# PMP20873E1_Bias.net
KiCad netlist of a schematic drawn in Altium Designer
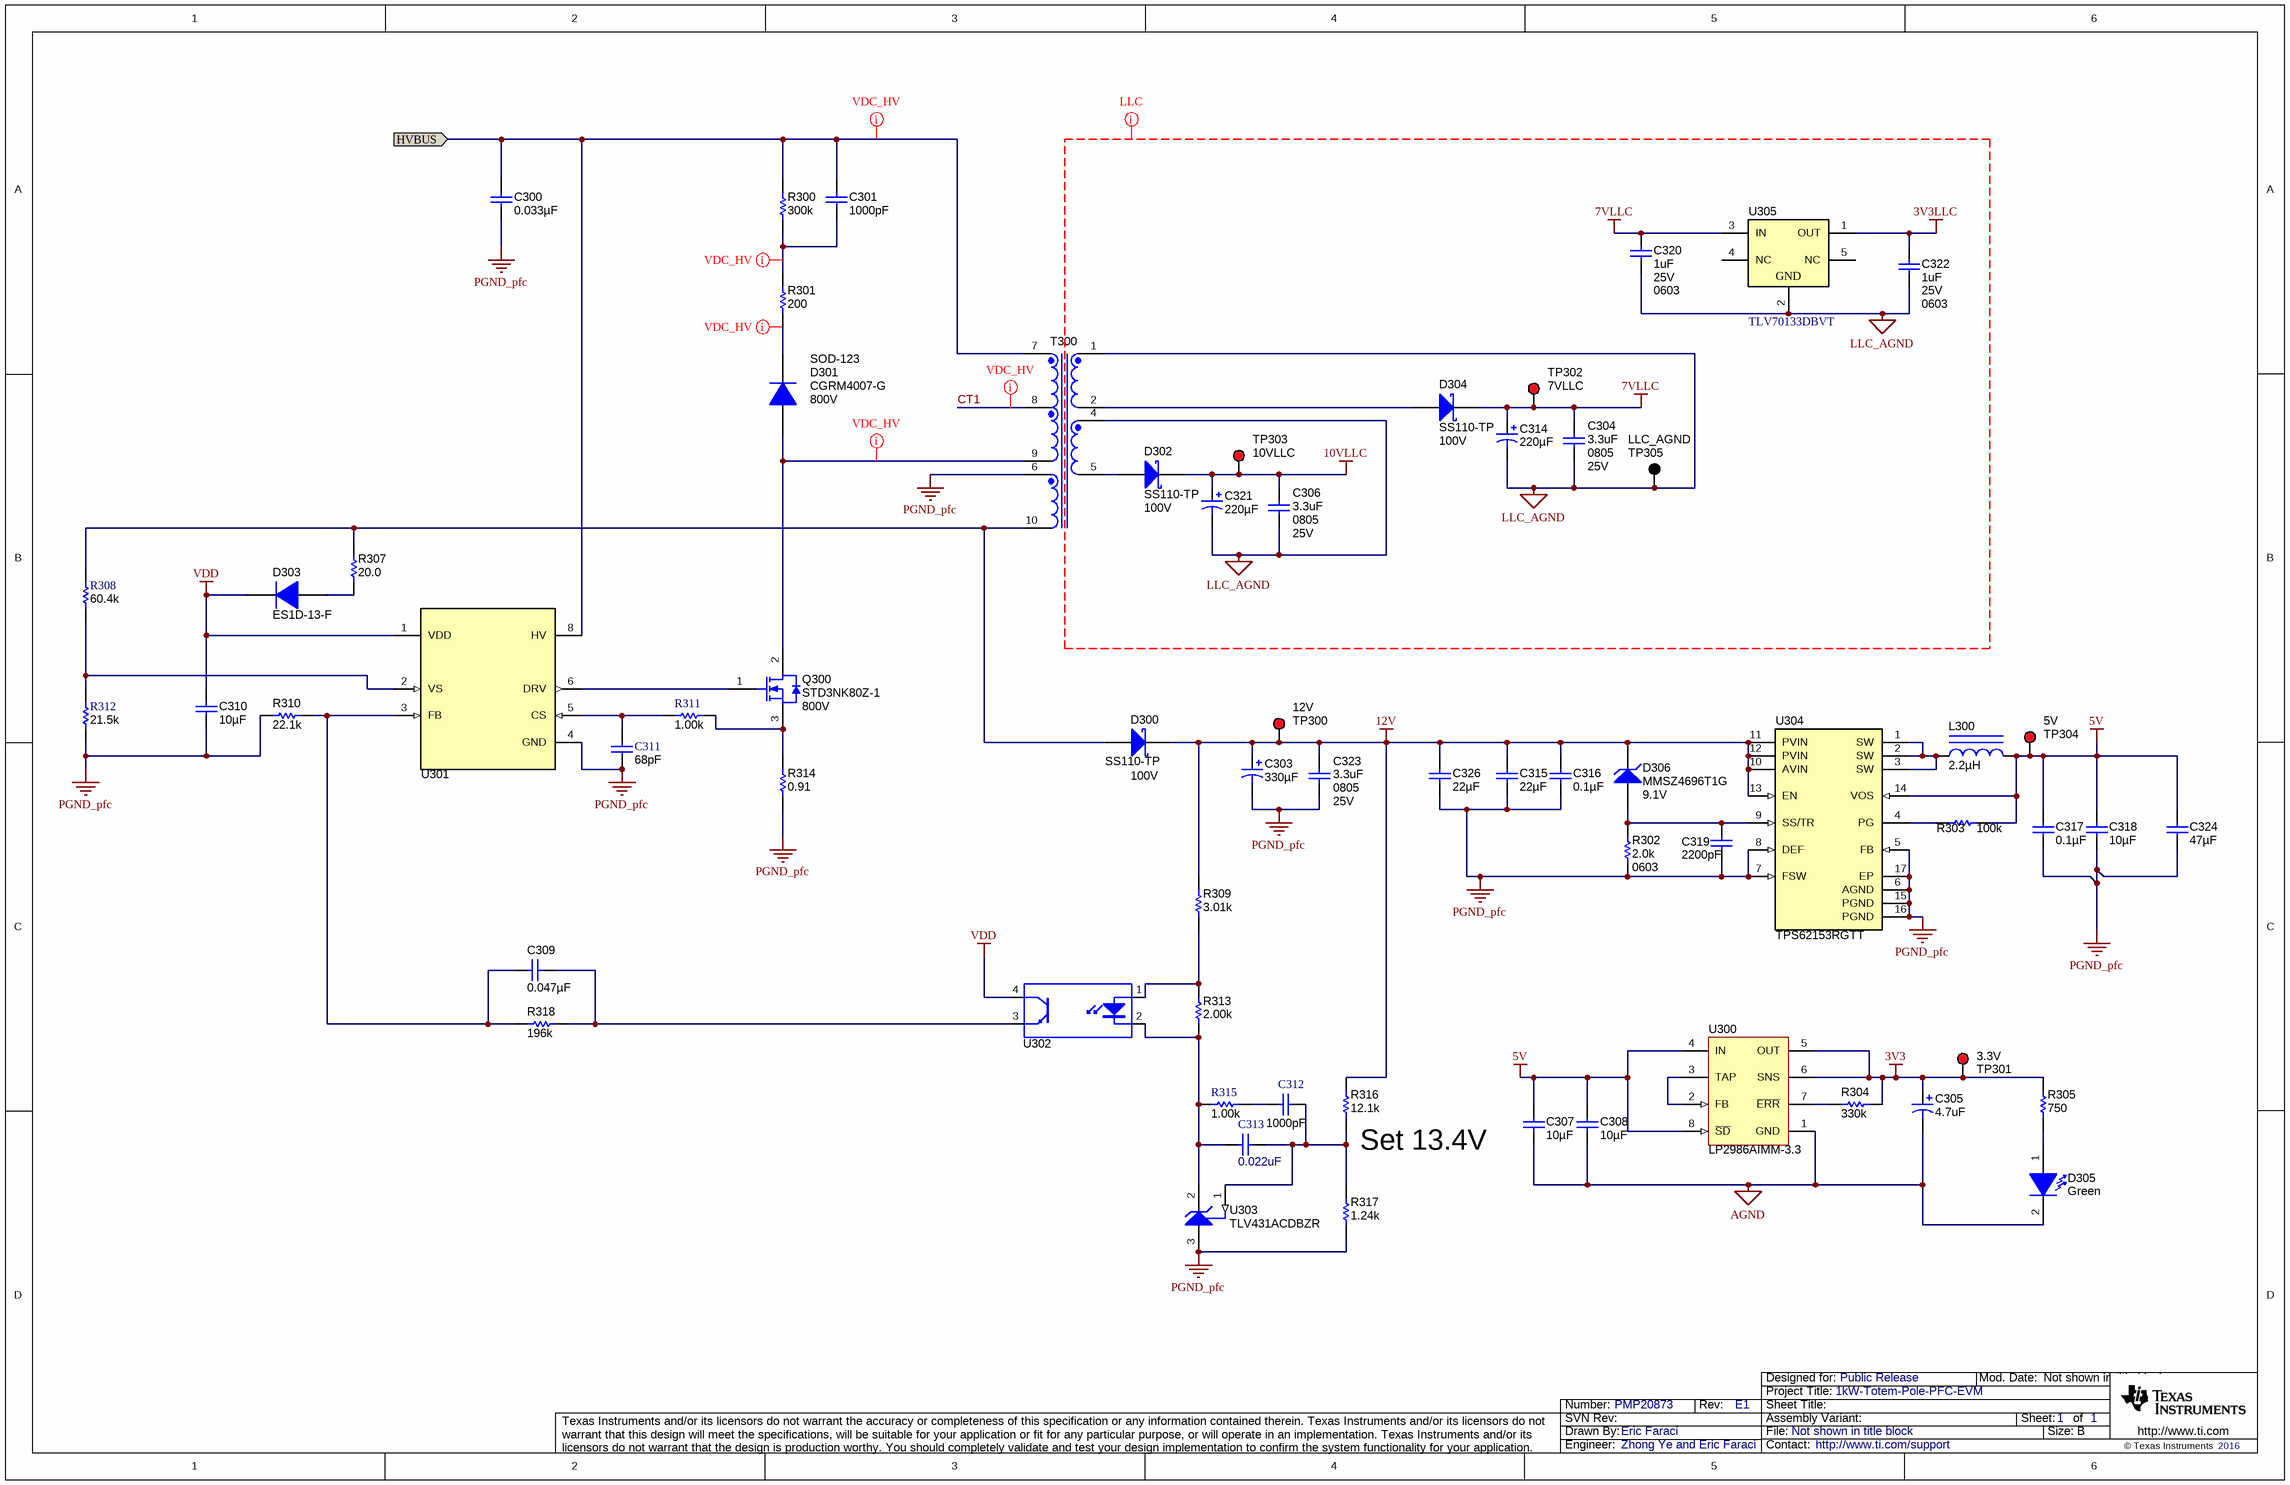
[diagram p0: PMP20873E1_Bias.SchDoc]

(export (version "E")
  (design (tool "Eeschema 10.0.6"))
  (components
    (comp (ref "C300")
      (value "GRM32DR72J333KW01L")
      (footprint "1210")
      (description "CAP, CERM, 0.033 µF, 630 V, +/- 10%, X7R, 1210")
      (fields
        (field (name "VALUEDISPLAYED") "0.033µF")
        (field (name "MANUFACTURER") "MuRata")
        (field (name "PUBLISHER") "Texas Instruments")
      )
      (libsource (lib "Capacitor_Ceramic") (part "GRM32DR72J333KW01L"))
    )
    (comp (ref "C301")
      (value "C2012X7R2E102K")
      (footprint "0805_HV")
      (description "CAP, CERM, 1000 pF, 250 V, +/- 10%, X7R, 0805")
      (fields
        (field (name "VALUEDISPLAYED") "1000pF")
        (field (name "MANUFACTURER") "TDK")
        (field (name "PUBLISHER") "Texas Instruments")
      )
      (libsource (lib "Capacitor_Ceramic") (part "C2012X7R2E102K"))
    )
    (comp (ref "C303")
      (value "25ZL330MEFC10X12.5")
      (footprint "ZL_1000x1250")
      (description "CAP, AL, 330 µF, 25 V, +/- 20%, 0.053 ohm, TH")
      (fields
        (field (name "VALUEDISPLAYED") "330µF")
        (field (name "MANUFACTURER") "Rubycon")
        (field (name "PUBLISHER") "Texas Instruments")
      )
      (libsource (lib "Capacitor_Aluminum") (part "25ZL330MEFC10X12.5"))
    )
    (comp (ref "C304")
      (value "GRM21BR71E335KA73L")
      (footprint "0805_HV")
      (description "CAP, CERM, 3.3uF, 25V, +/-10%, X7R, 0805")
      (fields
        (field (name "VALUEDISPLAYED") "3.3uF")
        (field (name "MANUFACTURER") "MuRata")
        (field (name "PACKAGEREFERENCE") "0805")
        (field (name "VALUE2") "25V")
        (field (name "PUBLISHER") "Texas Instruments")
      )
      (libsource (lib "Capacitor_Ceramic") (part "GRM21BR71E335KA73L"))
    )
    (comp (ref "C305")
      (value "293D475X9010B2TE3")
      (footprint "3528-21")
      (description "CAP, TA, 4.7uF, 10V, +/-10%, 3.4 ohm, SMD")
      (fields
        (field (name "VALUEDISPLAYED") "4.7uF")
        (field (name "MANUFACTURER") "Vishay-Sprague")
        (field (name "PUBLISHER") "Texas Instruments")
      )
      (libsource (lib "Capacitor_Tantalum") (part "293D475X9010B2TE3"))
    )
    (comp (ref "C306")
      (value "GRM21BR71E335KA73L")
      (footprint "0805_HV")
      (description "CAP, CERM, 3.3uF, 25V, +/-10%, X7R, 0805")
      (fields
        (field (name "VALUEDISPLAYED") "3.3uF")
        (field (name "MANUFACTURER") "MuRata")
        (field (name "PACKAGEREFERENCE") "0805")
        (field (name "VALUE2") "25V")
        (field (name "PUBLISHER") "Texas Instruments")
      )
      (libsource (lib "Capacitor_Ceramic") (part "GRM21BR71E335KA73L"))
    )
    (comp (ref "C307")
      (value "C0805C106K8PACTU")
      (footprint "0805_HV")
      (description "CAP, CERM, 10 µF, 10 V, +/- 10%, X5R, 0805")
      (fields
        (field (name "VALUEDISPLAYED") "10µF")
        (field (name "MANUFACTURER") "Kemet")
        (field (name "PUBLISHER") "Texas Instruments")
      )
      (libsource (lib "Capacitor_Ceramic") (part "C0805C106K8PACTU"))
    )
    (comp (ref "C308")
      (value "C0805C106K8PACTU")
      (footprint "0805_HV")
      (description "CAP, CERM, 10 µF, 10 V, +/- 10%, X5R, 0805")
      (fields
        (field (name "VALUEDISPLAYED") "10µF")
        (field (name "MANUFACTURER") "Kemet")
        (field (name "PUBLISHER") "Texas Instruments")
      )
      (libsource (lib "Capacitor_Ceramic") (part "C0805C106K8PACTU"))
    )
    (comp (ref "C309")
      (value "C0805C473K5RACTU")
      (footprint "0805_HV")
      (description "CAP, CERM, 0.047 µF, 50 V, +/- 10%, X7R, 0805")
      (fields
        (field (name "VALUEDISPLAYED") "0.047µF")
        (field (name "MANUFACTURER") "Kemet")
        (field (name "PUBLISHER") "Texas Instruments")
      )
      (libsource (lib "Capacitor_Ceramic") (part "C0805C473K5RACTU"))
    )
    (comp (ref "C310")
      (value "GRM31CR71E106KA12L")
      (footprint "1206")
      (description "CAP, CERM, 10 µF, 25 V, +/- 10%, X7R, 1206")
      (fields
        (field (name "VALUEDISPLAYED") "10µF")
        (field (name "MANUFACTURER") "MuRata")
        (field (name "PUBLISHER") "Texas Instruments")
      )
      (libsource (lib "Capacitor_Ceramic") (part "GRM31CR71E106KA12L"))
    )
    (comp (ref "C311")
      (value "06035A680JAT2A")
      (footprint "0603")
      (description "CAP, CERM, 68pF, 50V, +/-5%, C0G/NP0, 0603")
      (fields
        (field (name "VALUEDISPLAYED") "68pF")
        (field (name "MANUFACTURER") "AVX")
        (field (name "PUBLISHER") "Texas Instruments")
      )
      (libsource (lib "Capacitor_Ceramic") (part "06035A680JAT2A"))
    )
    (comp (ref "C312")
      (value "06035A102KAT2A")
      (footprint "0603")
      (description "CAP, CERM, 1000pF, 50V, +/-10%, C0G/NP0, 0603")
      (fields
        (field (name "VALUEDISPLAYED") "1000pF")
        (field (name "MANUFACTURER") "AVX")
        (field (name "PUBLISHER") "Texas Instruments")
      )
      (libsource (lib "Capacitor_Ceramic") (part "06035A102KAT2A"))
    )
    (comp (ref "C313")
      (value "C0603C223K3RACTU")
      (footprint "0603")
      (description "CAP, CERM, 0.022uF, 25V, +/-10%, X7R, 0603")
      (fields
        (field (name "VALUEDISPLAYED") "0.022uF")
        (field (name "MANUFACTURER") "Kemet")
        (field (name "PUBLISHER") "Texas Instruments")
      )
      (libsource (lib "Capacitor_Ceramic") (part "C0603C223K3RACTU"))
    )
    (comp (ref "C314")
      (value "TPSV227K016R0050")
      (footprint "7361-38")
      (description "CAP, TA, 220 µF, 16 V, +/- 10%, 0.05 ohm, SMD")
      (fields
        (field (name "VALUEDISPLAYED") "220µF")
        (field (name "MANUFACTURER") "AVX")
        (field (name "PUBLISHER") "Texas Instruments")
      )
      (libsource (lib "Capacitor_Tantalum") (part "TPSV227K016R0050"))
    )
    (comp (ref "C315")
      (value "1206YD226MAT2A")
      (footprint "1206")
      (description "CAP, CERM, 22 µF, 16 V, +/- 20%, X5R, 1206")
      (fields
        (field (name "VALUEDISPLAYED") "22µF")
        (field (name "MANUFACTURER") "AVX")
        (field (name "PUBLISHER") "Texas Instruments")
      )
      (libsource (lib "Capacitor_Ceramic") (part "1206YD226MAT2A"))
    )
    (comp (ref "C316")
      (value "C1005X7R1H104K")
      (footprint "0402")
      (description "CAP, CERM, 0.1uF, 50V, +/-10%, C0G/NP0, 0402")
      (fields
        (field (name "VALUEDISPLAYED") "0.1µF")
        (field (name "MANUFACTURER") "TDK")
        (field (name "PUBLISHER") "Texas Instruments")
      )
      (libsource (lib "Capacitor_Ceramic") (part "C1005X7R1H104K"))
    )
    (comp (ref "C317")
      (value "C1005X7R1H104K")
      (footprint "0402")
      (description "CAP, CERM, 0.1uF, 50V, +/-10%, C0G/NP0, 0402")
      (fields
        (field (name "VALUEDISPLAYED") "0.1µF")
        (field (name "MANUFACTURER") "TDK")
        (field (name "PUBLISHER") "Texas Instruments")
      )
      (libsource (lib "Capacitor_Ceramic") (part "C1005X7R1H104K"))
    )
    (comp (ref "C318")
      (value "GRM21BR71A106KE51L")
      (footprint "0805_HV")
      (description "CAP, CERM, 10uF, 10V, +/-10%, X7R, 0805")
      (fields
        (field (name "VALUEDISPLAYED") "10µF")
        (field (name "MANUFACTURER") "MuRata")
        (field (name "PUBLISHER") "Texas Instruments")
      )
      (libsource (lib "Capacitor_Ceramic") (part "GRM21BR71A106KE51L"))
    )
    (comp (ref "C319")
      (value "GRM155R71E222KA01D")
      (footprint "0402")
      (description "CAP, CERM, 2200pF, 25V, +10/%, X7R, 0402")
      (fields
        (field (name "VALUEDISPLAYED") "2200pF")
        (field (name "MANUFACTURER") "MuRata")
        (field (name "PUBLISHER") "Texas Instruments")
      )
      (libsource (lib "Capacitor_Ceramic") (part "GRM155R71E222KA01D"))
    )
    (comp (ref "C320")
      (value "C1608X7R1E105K080AB")
      (footprint "0603")
      (description "CAP, CERM, 1uF, 25V, +/-10%, X7R, 0603")
      (fields
        (field (name "VALUEDISPLAYED") "1uF")
        (field (name "MANUFACTURER") "TDK")
        (field (name "VALUE2") "25V")
        (field (name "CAP_CASE") "0603")
        (field (name "PUBLISHER") "Texas Instruments")
      )
      (libsource (lib "Capacitor_Ceramic") (part "C1608X7R1E105K080AB"))
    )
    (comp (ref "C321")
      (value "TPSV227K016R0050")
      (footprint "7361-38")
      (description "CAP, TA, 220 µF, 16 V, +/- 10%, 0.05 ohm, SMD")
      (fields
        (field (name "VALUEDISPLAYED") "220µF")
        (field (name "MANUFACTURER") "AVX")
        (field (name "PUBLISHER") "Texas Instruments")
      )
      (libsource (lib "Capacitor_Tantalum") (part "TPSV227K016R0050"))
    )
    (comp (ref "C322")
      (value "C1608X7R1E105K080AB")
      (footprint "0603")
      (description "CAP, CERM, 1uF, 25V, +/-10%, X7R, 0603")
      (fields
        (field (name "VALUEDISPLAYED") "1uF")
        (field (name "MANUFACTURER") "TDK")
        (field (name "VALUE2") "25V")
        (field (name "CAP_CASE") "0603")
        (field (name "PUBLISHER") "Texas Instruments")
      )
      (libsource (lib "Capacitor_Ceramic") (part "C1608X7R1E105K080AB"))
    )
    (comp (ref "C323")
      (value "GRM21BR71E335KA73L")
      (footprint "0805_HV")
      (description "CAP, CERM, 3.3uF, 25V, +/-10%, X7R, 0805")
      (fields
        (field (name "VALUEDISPLAYED") "3.3uF")
        (field (name "MANUFACTURER") "MuRata")
        (field (name "PACKAGEREFERENCE") "0805")
        (field (name "VALUE2") "25V")
        (field (name "PUBLISHER") "Texas Instruments")
      )
      (libsource (lib "Capacitor_Ceramic") (part "GRM21BR71E335KA73L"))
    )
    (comp (ref "C324")
      (value "12106D476MAT2A")
      (footprint "1210")
      (description "CAP, CERM, 47 µF, 6.3 V, +/- 20%, X5R, 1210")
      (fields
        (field (name "VALUEDISPLAYED") "47µF")
        (field (name "MANUFACTURER") "AVX")
        (field (name "PUBLISHER") "Texas Instruments")
      )
      (libsource (lib "Capacitor_Ceramic") (part "12106D476MAT2A"))
    )
    (comp (ref "C326")
      (value "1206YD226MAT2A")
      (footprint "1206")
      (description "CAP, CERM, 22 µF, 16 V, +/- 20%, X5R, 1206")
      (fields
        (field (name "VALUEDISPLAYED") "22µF")
        (field (name "MANUFACTURER") "AVX")
        (field (name "PUBLISHER") "Texas Instruments")
      )
      (libsource (lib "Capacitor_Ceramic") (part "1206YD226MAT2A"))
    )
    (comp (ref "D300")
      (value "SS110-TP")
      (footprint "SMA")
      (description "Diode, Schottky, 100V, 1A, SMB")
      (fields
        (field (name "ALTIUM_VALUE") "100V")
        (field (name "MANUFACTURER") "International Rectifier")
        (field (name "PUBLISHER") "Texas Instruments")
      )
      (libsource (lib "Diode") (part "10BQ100TRPBF"))
    )
    (comp (ref "D301")
      (value "CGRM4007-G")
      (footprint "SOD-123")
      (description "Diode, Ultrafast, 800V, 1A, SMA")
      (fields
        (field (name "MANUFACTURER") "Diodes Inc.")
        (field (name "PACKAGEREFERENCE") "SOD-123")
        (field (name "VALUE2") "800V")
        (field (name "PUBLISHER") "Texas Instruments")
      )
      (libsource (lib "Diode") (part "US1M-13-F"))
    )
    (comp (ref "D302")
      (value "SS110-TP")
      (footprint "SMA")
      (description "Diode, Schottky, 100V, 1A, SMB")
      (fields
        (field (name "ALTIUM_VALUE") "100V")
        (field (name "MANUFACTURER") "International Rectifier")
        (field (name "PUBLISHER") "Texas Instruments")
      )
      (libsource (lib "Diode") (part "10BQ100TRPBF"))
    )
    (comp (ref "D303")
      (value "ES1D-13-F")
      (footprint "SMA")
      (description "Diode, Ultrafast, 200 V, 1 A, SMA")
      (fields (field (name "MANUFACTURER") "Diodes Inc.") (field (name "PUBLISHER") "Texas Instruments"))
      (libsource (lib "Diode") (part "ES1D-13-F"))
    )
    (comp (ref "D304")
      (value "SS110-TP")
      (footprint "SMA")
      (description "Diode, Schottky, 100V, 1A, SMB")
      (fields
        (field (name "ALTIUM_VALUE") "100V")
        (field (name "MANUFACTURER") "International Rectifier")
        (field (name "PUBLISHER") "Texas Instruments")
      )
      (libsource (lib "Diode") (part "10BQ100TRPBF"))
    )
    (comp (ref "D305")
      (value "Green")
      (footprint "LG L29K_GREEN")
      (description "LED, Green, SMD")
      (fields
        (field (name "MANUFACTURER") "OSRAM")
        (field (name "PARTNUMBER") "LG L29K-G2J1-24-Z")
        (field (name "PUBLISHER") "Texas Instruments")
      )
      (libsource (lib "LED") (part "LG L29K-G2J1-24-Z"))
    )
    (comp (ref "D306")
      (value "MMSZ4696T1G")
      (footprint "SOD-123")
      (description "Diode, Zener, 9.1 V, 500 mW, SOD-123")
      (fields
        (field (name "ALTIUM_VALUE") "9.1V")
        (field (name "MANUFACTURER") "ON Semiconductor")
        (field (name "SYMBOLCREATOR") "a0412235")
        (field (name "PUBLISHER") "Texas Instruments")
      )
      (libsource (lib "ZenerDiodes") (part "MMSZ4696T1G"))
    )
    (comp (ref "L300")
      (value "SDR0403-2R2ML")
      (footprint "SDR0403")
      (description "Inductor, Drum Core, Ferrite, 2.2 µH, 2.6 A, 0.047 ohm, SMD")
      (fields
        (field (name "VALUEDISPLAYED") "2.2µH")
        (field (name "MANUFACTURER") "Bourns")
        (field (name "PUBLISHER") "Texas Instruments")
      )
      (libsource (lib "Inductor_Bourns") (part "SDR0403-2R2ML"))
    )
    (comp (ref "Q300")
      (value "STD3NK80Z-1")
      (footprint "IPAK")
      (description "MOSFET, N-CH, 800V, 2.5A, IPAK")
      (fields
        (field (name "ALTIUM_VALUE") "800V")
        (field (name "MANUFACTURER") "ST Microelectronics")
        (field (name "PUBLISHER") "Texas Instruments")
      )
      (libsource (lib "FETs") (part "STD3NK80Z-1"))
    )
    (comp (ref "R300")
      (value "RC1206FR-07300KL")
      (footprint "1206")
      (description "RES, 300 k, 1%, 0.25 W, 1206")
      (fields
        (field (name "VALUEDISPLAYED") "300k")
        (field (name "MANUFACTURER") "Yageo America")
        (field (name "PUBLISHER") "Texas Instruments")
      )
      (libsource (lib "Resistor_1206") (part "RC1206FR-07300KL"))
    )
    (comp (ref "R301")
      (value "ERJ-6GEYJ201V")
      (footprint "0805_HV")
      (description "RES, 200, 5%, 0.125 W, 0805")
      (fields
        (field (name "VALUEDISPLAYED") "200")
        (field (name "MANUFACTURER") "Panasonic")
        (field (name "PUBLISHER") "Texas Instruments")
      )
      (libsource (lib "Resistor_0805") (part "ERJ-6GEYJ201V"))
    )
    (comp (ref "R302")
      (value "2.0k")
      (footprint "0603")
      (description "RES, 2.0k ohm, 5%, 0.1W, 0603")
      (fields
        (field (name "PARTNUMBER") "CRCW06032K00JNEA")
        (field (name "MANUFACTURER") "Vishay-Dale")
        (field (name "PACKAGEREFERENCE") "0603")
        (field (name "PUBLISHER") "Texas Instruments")
      )
      (libsource (lib "Resistor_0603") (part "CRCW06032K00JNEA"))
    )
    (comp (ref "R303")
      (value "100k")
      (footprint "0402")
      (description "RES, 100k ohm, 1%, 0.063W, 0402")
      (fields
        (field (name "PARTNUMBER") "CRCW0402100KFKED")
        (field (name "MANUFACTURER") "Vishay-Dale")
        (field (name "PUBLISHER") "Texas Instruments")
      )
      (libsource (lib "Resistor_0402") (part "CRCW0402100KFKED"))
    )
    (comp (ref "R304")
      (value "RG1608P-334-B-T5")
      (footprint "0603")
      (description "RES, 330 k, 0.1%, 0.1 W, 0603")
      (fields
        (field (name "VALUEDISPLAYED") "330k")
        (field (name "MANUFACTURER") "Susumu Co Ltd")
        (field (name "PUBLISHER") "Texas Instruments")
      )
      (libsource (lib "Resistor_0603") (part "RG1608P-334-B-T5"))
    )
    (comp (ref "R305")
      (value "RT0603DRE07750RL")
      (footprint "0603")
      (description "RES, 750, 0.5%, 0.1 W, 0603")
      (fields
        (field (name "VALUEDISPLAYED") "750")
        (field (name "MANUFACTURER") "Yageo America")
        (field (name "PUBLISHER") "Texas Instruments")
      )
      (libsource (lib "Resistor_0603") (part "RT0603DRE07750RL"))
    )
    (comp (ref "R307")
      (value "RC0603FR-0720RL")
      (footprint "0603")
      (description "RES, 20.0, 1%, 0.1 W, 0603")
      (fields
        (field (name "VALUEDISPLAYED") "20.0")
        (field (name "MANUFACTURER") "Yageo America")
        (field (name "PUBLISHER") "Texas Instruments")
      )
      (libsource (lib "Resistor_0603") (part "RC0603FR-0720RL"))
    )
    (comp (ref "R308")
      (value "60.4k")
      (footprint "0603")
      (description "RES, 60.4k ohm, 1%, 0.1W, 0603")
      (fields
        (field (name "PARTNUMBER") "CRCW060360K4FKEA")
        (field (name "MANUFACTURER") "Vishay-Dale")
        (field (name "PUBLISHER") "Texas Instruments")
      )
      (libsource (lib "Resistor_0603") (part "CRCW060360K4FKEA"))
    )
    (comp (ref "R309")
      (value "CRCW08053K01FKEA")
      (footprint "0805_HV")
      (description "RES, 3.01 k, 1%, 0.125 W, 0805")
      (fields
        (field (name "VALUEDISPLAYED") "3.01k")
        (field (name "MANUFACTURER") "Vishay-Dale")
        (field (name "PUBLISHER") "Texas Instruments")
      )
      (libsource (lib "Resistor_0805") (part "CRCW08053K01FKEA"))
    )
    (comp (ref "R310")
      (value "CRCW080522K1FKEA")
      (footprint "0805_HV")
      (description "RES, 22.1 k, 1%, 0.125 W, 0805")
      (fields
        (field (name "VALUEDISPLAYED") "22.1k")
        (field (name "MANUFACTURER") "Vishay-Dale")
        (field (name "PUBLISHER") "Texas Instruments")
      )
      (libsource (lib "Resistor_0805") (part "CRCW080522K1FKEA"))
    )
    (comp (ref "R311")
      (value "1.00k")
      (footprint "0603")
      (description "RES, 1.00k ohm, 1%, 0.1W, 0603")
      (fields
        (field (name "PARTNUMBER") "CRCW06031K00FKEA")
        (field (name "MANUFACTURER") "Vishay-Dale")
        (field (name "PUBLISHER") "Texas Instruments")
      )
      (libsource (lib "Resistor_0603") (part "CRCW06031K00FKEA"))
    )
    (comp (ref "R312")
      (value "21.5k")
      (footprint "0603")
      (description "RES, 21.5k ohm, 1%, 0.1W, 0603")
      (fields
        (field (name "PARTNUMBER") "CRCW060321K5FKEA")
        (field (name "MANUFACTURER") "Vishay-Dale")
        (field (name "PUBLISHER") "Texas Instruments")
      )
      (libsource (lib "Resistor_0603") (part "CRCW060321K5FKEA"))
    )
    (comp (ref "R313")
      (value "CRCW08052K00FKEA")
      (footprint "0805_HV")
      (description "RES, 2.00 k, 1%, 0.125 W, 0805")
      (fields
        (field (name "VALUEDISPLAYED") "2.00k")
        (field (name "MANUFACTURER") "Vishay-Dale")
        (field (name "PUBLISHER") "Texas Instruments")
      )
      (libsource (lib "Resistor_0805") (part "CRCW08052K00FKEA"))
    )
    (comp (ref "R314")
      (value "CRM0805-FX-R910ELF")
      (footprint "0805_HV")
      (description "RES, 0.91, 1%, 0.25 W, 0805")
      (fields
        (field (name "VALUEDISPLAYED") "0.91")
        (field (name "MANUFACTURER") "Bourns")
        (field (name "PUBLISHER") "Texas Instruments")
      )
      (libsource (lib "Resistor_0805") (part "CRM0805-FX-R910ELF"))
    )
    (comp (ref "R315")
      (value "1.00k")
      (footprint "0603")
      (description "RES, 1.00k ohm, 1%, 0.1W, 0603")
      (fields
        (field (name "PARTNUMBER") "CRCW06031K00FKEA")
        (field (name "MANUFACTURER") "Vishay-Dale")
        (field (name "PUBLISHER") "Texas Instruments")
      )
      (libsource (lib "Resistor_0603") (part "CRCW06031K00FKEA"))
    )
    (comp (ref "R316")
      (value "CRCW080512K1FKEA")
      (footprint "0805_HV")
      (description "RES, 12.1 k, 1%, 0.125 W, 0805")
      (fields
        (field (name "VALUEDISPLAYED") "12.1k")
        (field (name "MANUFACTURER") "Vishay-Dale")
        (field (name "PUBLISHER") "Texas Instruments")
      )
      (libsource (lib "Resistor_0805") (part "CRCW080512K1FKEA"))
    )
    (comp (ref "R317")
      (value "CRCW08051K24FKEA")
      (footprint "0805_HV")
      (description "RES, 1.24 k, 1%, 0.125 W, 0805")
      (fields
        (field (name "VALUEDISPLAYED") "1.24k")
        (field (name "MANUFACTURER") "Vishay-Dale")
        (field (name "PUBLISHER") "Texas Instruments")
      )
      (libsource (lib "Resistor_0805") (part "CRCW08051K24FKEA"))
    )
    (comp (ref "R318")
      (value "ERJ-6ENF1963V")
      (footprint "0805_HV")
      (description "RES, 196 k, 1%, 0.125 W, 0805")
      (fields
        (field (name "VALUEDISPLAYED") "196k")
        (field (name "MANUFACTURER") "Panasonic")
        (field (name "PUBLISHER") "Texas Instruments")
      )
      (libsource (lib "Resistor_0805") (part "ERJ-6ENF1963V"))
    )
    (comp (ref "T300")
      (value "750315894")
      (footprint "Wurth_750315894")
      (description "Transformer, 13 mH, TH")
      (fields
        (field (name "MANUFACTURER") "Wurth Elektronik")
        (field (name "SYMBOLCREATOR") "Altium")
        (field (name "PUBLISHER") "Texas Instruments")
      )
      (libsource (lib "Transformers") (part "750315894"))
    )
    (comp (ref "TP300")
      (value "12V")
      (footprint "Keystone5000")
      (description "Test Point, Miniature, Red, TH")
      (fields
        (field (name "PARTNUMBER") "5000")
        (field (name "MANUFACTURER") "Keystone")
        (field (name "PUBLISHER") "Texas Instruments")
      )
      (libsource (lib "Connectors_Keystone") (part "5000"))
    )
    (comp (ref "TP301")
      (value "3.3V")
      (footprint "Keystone5000")
      (description "Test Point, Miniature, Red, TH")
      (fields
        (field (name "PARTNUMBER") "5000")
        (field (name "MANUFACTURER") "Keystone")
        (field (name "PUBLISHER") "Texas Instruments")
      )
      (libsource (lib "Connectors_Keystone") (part "5000"))
    )
    (comp (ref "TP302")
      (value "7VLLC")
      (footprint "Keystone5000")
      (description "Test Point, Miniature, Red, TH")
      (fields
        (field (name "PARTNUMBER") "5000")
        (field (name "MANUFACTURER") "Keystone")
        (field (name "PUBLISHER") "Texas Instruments")
      )
      (libsource (lib "Connectors_Keystone") (part "5000"))
    )
    (comp (ref "TP303")
      (value "10VLLC")
      (footprint "Keystone5000")
      (description "Test Point, Miniature, Red, TH")
      (fields
        (field (name "PARTNUMBER") "5000")
        (field (name "MANUFACTURER") "Keystone")
        (field (name "PUBLISHER") "Texas Instruments")
      )
      (libsource (lib "Connectors_Keystone") (part "5000"))
    )
    (comp (ref "TP304")
      (value "5V")
      (footprint "Keystone5000")
      (description "Test Point, Miniature, Red, TH")
      (fields
        (field (name "PARTNUMBER") "5000")
        (field (name "MANUFACTURER") "Keystone")
        (field (name "PUBLISHER") "Texas Instruments")
      )
      (libsource (lib "Connectors_Keystone") (part "5000"))
    )
    (comp (ref "TP305")
      (value "LLC_AGND")
      (footprint "Keystone5001")
      (description "Test Point, Miniature, Black, TH")
      (fields
        (field (name "PARTNUMBER") "5001")
        (field (name "MANUFACTURER") "Keystone")
        (field (name "PUBLISHER") "Texas Instruments")
      )
      (libsource (lib "Connectors_Keystone") (part "5001"))
    )
    (comp (ref "U300")
      (value "LP2986AIMM-3.3")
      (footprint "MUA08A_N")
      (description "Micropower, 200 mA Ultra Low-Dropout Fixed or Adjustable Voltage Regulator, 8-pin Mini SOIC")
      (fields
        (field (name "MANUFACTURER") "National Semiconductor")
        (field (name "PUBLISHER") "Altium Limited")
      )
      (libsource (lib "NSC LDO") (part "LP2986AIMM-3.3"))
    )
    (comp (ref "U301")
      (value "UCC28740DR")
      (footprint "D0007A_N")
      (description "Constant-Voltage, Constant-Current Flyback Controller Using Opto-Coupler Feedback, D0007A")
      (fields
        (field (name "ALTERNATE PARTNUMBER") "UCC28740D")
        (field (name "MANUFACTURER") "Texas Instruments")
        (field (name "SYMBOLCREATOR") "a0412235")
        (field (name "PUBLISHER") "Texas Instruments")
      )
      (libsource (lib "TI_Pre_Release") (part "UCC28740DR"))
    )
    (comp (ref "U302")
      (value "LTV-817S")
      (footprint "DIP254P762X350-4")
      (description "Optocoupler, 5 kV, 50-600% CTR, TH-4")
      (fields (field (name "MANUFACTURER") "Lite-On") (field (name "PUBLISHER") "Texas Instruments"))
      (libsource (lib "OptoCouplers") (part "LTV-817S"))
    )
    (comp (ref "U303")
      (value "TLV431ACDBZR")
      (footprint "DBZ0003A_N")
      (fields
        (field (name "MANUFACTURER") "Texas Instruments")
        (field (name "ALTERNATE PARTNUMBER") "Equivalent")
      )
      (libsource (lib "TI Power Management Shunt Voltage Reference") (part "TLV431ACDBZR"))
    )
    (comp (ref "U304")
      (value "TPS62153RGTT")
      (footprint "RGT0016C")
      (fields
        (field (name "MANUFACTURER") "Texas Instruments")
        (field (name "ALTERNATE PARTNUMBER") "Equivalent")
      )
      (libsource (lib "TI Power Management Step-Down Regulator") (part "TPS62153RGTT"))
    )
    (comp (ref "U305")
      (value "TLV70133DBVT")
      (footprint "DBV0005A_N")
      (fields
        (field (name "MANUFACTURER") "Texas Instruments")
        (field (name "ALTERNATE PARTNUMBER") "Equivalent")
      )
      (libsource (lib "TI Power Management Linear Regulator Single Channel LDO (0-350mA)") (part "TLV70133DBVT"))
    )
  )
  (nets
    (net (code "1") (name "/CT1") (class "Default")
      (node (ref "T300") (pin "8") (pinfunction "8_8") (pintype "passive"))
    )
    (net (code "2") (name "/HVBUS") (class "Default")
      (node (ref "C300") (pin "1") (pinfunction "1_1") (pintype "passive"))
      (node (ref "C301") (pin "1") (pinfunction "1_1") (pintype "passive"))
      (node (ref "R300") (pin "2") (pinfunction "2_2") (pintype "passive"))
      (node (ref "T300") (pin "7") (pinfunction "7_7") (pintype "passive"))
      (node (ref "U301") (pin "8") (pinfunction "HV_8") (pintype "power_in"))
    )
    (net (code "3") (name "3V3") (class "Default")
      (node (ref "C305") (pin "1") (pinfunction "+_1") (pintype "passive"))
      (node (ref "R304") (pin "2") (pinfunction "2_2") (pintype "passive"))
      (node (ref "R305") (pin "2") (pinfunction "2_2") (pintype "passive"))
      (node (ref "TP301") (pin "1") (pintype "passive"))
      (node (ref "U300") (pin "5") (pinfunction "OUT_5") (pintype "power_in"))
      (node (ref "U300") (pin "6") (pinfunction "SNS_6") (pintype "passive"))
    )
    (net (code "4") (name "3V3LLC") (class "Default")
      (node (ref "C322") (pin "2") (pinfunction "2_2") (pintype "passive"))
      (node (ref "U305") (pin "1") (pinfunction "OUT_1") (pintype "power_in"))
    )
    (net (code "5") (name "5V") (class "Default")
      (node (ref "C307") (pin "1") (pinfunction "1_1") (pintype "passive"))
      (node (ref "C308") (pin "1") (pinfunction "1_1") (pintype "passive"))
      (node (ref "C317") (pin "1") (pinfunction "1_1") (pintype "passive"))
      (node (ref "C318") (pin "2") (pinfunction "2_2") (pintype "passive"))
      (node (ref "C324") (pin "1") (pinfunction "1_1") (pintype "passive"))
      (node (ref "L300") (pin "2") (pinfunction "2_2") (pintype "passive"))
      (node (ref "R303") (pin "2") (pinfunction "2_2") (pintype "passive"))
      (node (ref "TP304") (pin "1") (pintype "passive"))
      (node (ref "U300") (pin "4") (pinfunction "IN_4") (pintype "power_in"))
      (node (ref "U300") (pin "8") (pinfunction "~{SD}_8") (pintype "input"))
      (node (ref "U304") (pin "14") (pinfunction "VOS_14") (pintype "input"))
    )
    (net (code "6") (name "7VLLC") (class "Default")
      (node (ref "C304") (pin "1") (pinfunction "1_1") (pintype "passive"))
      (node (ref "C314") (pin "1") (pinfunction "+_1") (pintype "passive"))
      (node (ref "C320") (pin "2") (pinfunction "2_2") (pintype "passive"))
      (node (ref "D304") (pin "1") (pinfunction "K_1") (pintype "passive"))
      (node (ref "TP302") (pin "1") (pintype "passive"))
      (node (ref "U305") (pin "3") (pinfunction "IN_3") (pintype "power_in"))
    )
    (net (code "7") (name "10VLLC") (class "Default")
      (node (ref "C306") (pin "1") (pinfunction "1_1") (pintype "passive"))
      (node (ref "C321") (pin "1") (pinfunction "+_1") (pintype "passive"))
      (node (ref "D302") (pin "1") (pinfunction "K_1") (pintype "passive"))
      (node (ref "TP303") (pin "1") (pintype "passive"))
    )
    (net (code "8") (name "12V") (class "Default")
      (node (ref "C303") (pin "1") (pinfunction "+_1") (pintype "passive"))
      (node (ref "C315") (pin "1") (pinfunction "1_1") (pintype "passive"))
      (node (ref "C316") (pin "1") (pinfunction "1_1") (pintype "passive"))
      (node (ref "C323") (pin "1") (pinfunction "1_1") (pintype "passive"))
      (node (ref "C326") (pin "1") (pinfunction "1_1") (pintype "passive"))
      (node (ref "D300") (pin "1") (pinfunction "K_1") (pintype "passive"))
      (node (ref "D306") (pin "1") (pinfunction "K_1") (pintype "passive"))
      (node (ref "R309") (pin "2") (pinfunction "2_2") (pintype "passive"))
      (node (ref "R316") (pin "2") (pinfunction "2_2") (pintype "passive"))
      (node (ref "TP300") (pin "1") (pintype "passive"))
      (node (ref "U304") (pin "10") (pinfunction "AVIN_10") (pintype "power_in"))
      (node (ref "U304") (pin "11") (pinfunction "PVIN_11") (pintype "power_in"))
      (node (ref "U304") (pin "12") (pinfunction "PVIN_12") (pintype "power_in"))
      (node (ref "U304") (pin "13") (pinfunction "EN_13") (pintype "input"))
    )
    (net (code "9") (name "AGND") (class "Default")
      (node (ref "C305") (pin "2") (pinfunction "-_2") (pintype "passive"))
      (node (ref "C307") (pin "2") (pinfunction "2_2") (pintype "passive"))
      (node (ref "C308") (pin "2") (pinfunction "2_2") (pintype "passive"))
      (node (ref "D305") (pin "2") (pinfunction "K_2") (pintype "passive"))
      (node (ref "U300") (pin "1") (pinfunction "GND_1") (pintype "power_in"))
    )
    (net (code "10") (name "LLC_AGND") (class "Default")
      (node (ref "C304") (pin "2") (pinfunction "2_2") (pintype "passive"))
      (node (ref "C306") (pin "2") (pinfunction "2_2") (pintype "passive"))
      (node (ref "C314") (pin "2") (pinfunction "-_2") (pintype "passive"))
      (node (ref "C320") (pin "1") (pinfunction "1_1") (pintype "passive"))
      (node (ref "C321") (pin "2") (pinfunction "-_2") (pintype "passive"))
      (node (ref "C322") (pin "1") (pinfunction "1_1") (pintype "passive"))
      (node (ref "T300") (pin "1") (pinfunction "1_1") (pintype "passive"))
      (node (ref "T300") (pin "4") (pinfunction "4_4") (pintype "passive"))
      (node (ref "TP305") (pin "1") (pintype "passive"))
      (node (ref "U305") (pin "2") (pinfunction "GND_2") (pintype "power_in"))
    )
    (net (code "11") (name "Net-(C301-Pad2)") (class "Default")
      (node (ref "C301") (pin "2") (pinfunction "2_2") (pintype "passive"))
      (node (ref "R300") (pin "1") (pinfunction "1_1") (pintype "passive"))
      (node (ref "R301") (pin "2") (pinfunction "2_2") (pintype "passive"))
    )
    (net (code "12") (name "Net-(C312-Pad2)") (class "Default")
      (node (ref "C312") (pin "2") (pinfunction "2_2") (pintype "passive"))
      (node (ref "R315") (pin "2") (pinfunction "2_2") (pintype "passive"))
    )
    (net (code "13") (name "Net-(D300-A)") (class "Default")
      (node (ref "D300") (pin "2") (pinfunction "A_2") (pintype "passive"))
      (node (ref "R307") (pin "2") (pinfunction "2_2") (pintype "passive"))
      (node (ref "R308") (pin "2") (pinfunction "2_2") (pintype "passive"))
      (node (ref "T300") (pin "10") (pinfunction "10_10") (pintype "passive"))
    )
    (net (code "14") (name "Net-(D301-A)") (class "Default")
      (node (ref "D301") (pin "2") (pinfunction "A_2") (pintype "passive"))
      (node (ref "Q300") (pin "2") (pinfunction "D_2") (pintype "passive"))
      (node (ref "T300") (pin "9") (pinfunction "9_9") (pintype "passive"))
    )
    (net (code "15") (name "Net-(D301-K)") (class "Default")
      (node (ref "D301") (pin "1") (pinfunction "K_1") (pintype "passive"))
      (node (ref "R301") (pin "1") (pinfunction "1_1") (pintype "passive"))
    )
    (net (code "16") (name "Net-(D302-A)") (class "Default")
      (node (ref "D302") (pin "2") (pinfunction "A_2") (pintype "passive"))
      (node (ref "T300") (pin "5") (pinfunction "5_5") (pintype "passive"))
    )
    (net (code "17") (name "Net-(D303-A)") (class "Default")
      (node (ref "D303") (pin "2") (pinfunction "A_2") (pintype "passive"))
      (node (ref "R307") (pin "1") (pinfunction "1_1") (pintype "passive"))
    )
    (net (code "18") (name "Net-(D304-A)") (class "Default")
      (node (ref "D304") (pin "2") (pinfunction "A_2") (pintype "passive"))
      (node (ref "T300") (pin "2") (pinfunction "2_2") (pintype "passive"))
    )
    (net (code "19") (name "Net-(D305-A)") (class "Default")
      (node (ref "D305") (pin "1") (pinfunction "A_1") (pintype "passive"))
      (node (ref "R305") (pin "1") (pinfunction "1_1") (pintype "passive"))
    )
    (net (code "20") (name "Net-(D306-A)") (class "Default")
      (node (ref "C319") (pin "1") (pinfunction "1_1") (pintype "passive"))
      (node (ref "D306") (pin "2") (pinfunction "A_2") (pintype "passive"))
      (node (ref "R302") (pin "1") (pinfunction "1_1") (pintype "passive"))
      (node (ref "U304") (pin "9") (pinfunction "SS/TR_9") (pintype "input"))
    )
    (net (code "21") (name "Net-(L300-Pad1)") (class "Default")
      (node (ref "L300") (pin "1") (pinfunction "1_1") (pintype "passive"))
      (node (ref "U304") (pin "1") (pinfunction "SW_1") (pintype "power_in"))
      (node (ref "U304") (pin "2") (pinfunction "SW_2") (pintype "power_in"))
      (node (ref "U304") (pin "3") (pinfunction "SW_3") (pintype "power_in"))
    )
    (net (code "22") (name "Net-(Q300-G)") (class "Default")
      (node (ref "Q300") (pin "1") (pinfunction "G_1") (pintype "passive"))
      (node (ref "U301") (pin "6") (pinfunction "DRV_6") (pintype "output"))
    )
    (net (code "23") (name "Net-(Q300-S)") (class "Default")
      (node (ref "Q300") (pin "3") (pinfunction "S_3") (pintype "passive"))
      (node (ref "R311") (pin "2") (pinfunction "2_2") (pintype "passive"))
      (node (ref "R314") (pin "2") (pinfunction "2_2") (pintype "passive"))
    )
    (net (code "24") (name "Net-(U300-FB)") (class "Default")
      (node (ref "U300") (pin "2") (pinfunction "FB_2") (pintype "input"))
      (node (ref "U300") (pin "3") (pinfunction "TAP_3") (pintype "passive"))
    )
    (net (code "25") (name "Net-(U300-~{ERR})") (class "Default")
      (node (ref "R304") (pin "1") (pinfunction "1_1") (pintype "passive"))
      (node (ref "U300") (pin "7") (pinfunction "~{ERR}_7") (pintype "open_collector"))
    )
    (net (code "26") (name "Net-(U301-CS)") (class "Default")
      (node (ref "C311") (pin "1") (pinfunction "1_1") (pintype "passive"))
      (node (ref "R311") (pin "1") (pinfunction "1_1") (pintype "passive"))
      (node (ref "U301") (pin "5") (pinfunction "CS_5") (pintype "input"))
    )
    (net (code "27") (name "Net-(U301-FB)") (class "Default")
      (node (ref "C309") (pin "2") (pinfunction "2_2") (pintype "passive"))
      (node (ref "R310") (pin "2") (pinfunction "2_2") (pintype "passive"))
      (node (ref "R318") (pin "1") (pinfunction "1_1") (pintype "passive"))
      (node (ref "U301") (pin "3") (pinfunction "FB_3") (pintype "input"))
    )
    (net (code "28") (name "Net-(U301-VS)") (class "Default")
      (node (ref "R308") (pin "1") (pinfunction "1_1") (pintype "passive"))
      (node (ref "R312") (pin "2") (pinfunction "2_2") (pintype "passive"))
      (node (ref "U301") (pin "2") (pinfunction "VS_2") (pintype "input"))
    )
    (net (code "29") (name "Net-(U302-A)") (class "Default")
      (node (ref "R309") (pin "1") (pinfunction "1_1") (pintype "passive"))
      (node (ref "R313") (pin "2") (pinfunction "2_2") (pintype "passive"))
      (node (ref "U302") (pin "1") (pinfunction "A_1") (pintype "passive"))
    )
    (net (code "30") (name "Net-(U302-E)") (class "Default")
      (node (ref "C309") (pin "1") (pinfunction "1_1") (pintype "passive"))
      (node (ref "R318") (pin "2") (pinfunction "2_2") (pintype "passive"))
      (node (ref "U302") (pin "3") (pinfunction "E_3") (pintype "passive"))
    )
    (net (code "31") (name "Net-(U302-K)") (class "Default")
      (node (ref "C313") (pin "2") (pinfunction "2_2") (pintype "passive"))
      (node (ref "R313") (pin "1") (pinfunction "1_1") (pintype "passive"))
      (node (ref "R315") (pin "1") (pinfunction "1_1") (pintype "passive"))
      (node (ref "U302") (pin "2") (pinfunction "K_2") (pintype "passive"))
      (node (ref "U303") (pin "2") (pinfunction "CATHODE_2") (pintype "passive"))
    )
    (net (code "32") (name "Net-(U303-REF)") (class "Default")
      (node (ref "C312") (pin "1") (pinfunction "1_1") (pintype "passive"))
      (node (ref "C313") (pin "1") (pinfunction "1_1") (pintype "passive"))
      (node (ref "R316") (pin "1") (pinfunction "1_1") (pintype "passive"))
      (node (ref "R317") (pin "2") (pinfunction "2_2") (pintype "passive"))
      (node (ref "U303") (pin "1") (pinfunction "REF_1") (pintype "input"))
    )
    (net (code "33") (name "Net-(U304-PG)") (class "Default")
      (node (ref "R303") (pin "1") (pinfunction "1_1") (pintype "passive"))
      (node (ref "U304") (pin "4") (pinfunction "PG_4") (pintype "tri_state"))
    )
    (net (code "34") (name "PGND_pfc") (class "Default")
      (node (ref "C300") (pin "2") (pinfunction "2_2") (pintype "passive"))
      (node (ref "C303") (pin "2") (pinfunction "-_2") (pintype "passive"))
      (node (ref "C310") (pin "2") (pinfunction "2_2") (pintype "passive"))
      (node (ref "C311") (pin "2") (pinfunction "2_2") (pintype "passive"))
      (node (ref "C315") (pin "2") (pinfunction "2_2") (pintype "passive"))
      (node (ref "C316") (pin "2") (pinfunction "2_2") (pintype "passive"))
      (node (ref "C317") (pin "2") (pinfunction "2_2") (pintype "passive"))
      (node (ref "C318") (pin "1") (pinfunction "1_1") (pintype "passive"))
      (node (ref "C319") (pin "2") (pinfunction "2_2") (pintype "passive"))
      (node (ref "C323") (pin "2") (pinfunction "2_2") (pintype "passive"))
      (node (ref "C324") (pin "2") (pinfunction "2_2") (pintype "passive"))
      (node (ref "C326") (pin "2") (pinfunction "2_2") (pintype "passive"))
      (node (ref "R302") (pin "2") (pinfunction "2_2") (pintype "passive"))
      (node (ref "R310") (pin "1") (pinfunction "1_1") (pintype "passive"))
      (node (ref "R312") (pin "1") (pinfunction "1_1") (pintype "passive"))
      (node (ref "R314") (pin "1") (pinfunction "1_1") (pintype "passive"))
      (node (ref "R317") (pin "1") (pinfunction "1_1") (pintype "passive"))
      (node (ref "T300") (pin "6") (pinfunction "6_6") (pintype "passive"))
      (node (ref "U301") (pin "4") (pinfunction "GND_4") (pintype "power_in"))
      (node (ref "U303") (pin "3") (pinfunction "ANODE_3") (pintype "passive"))
      (node (ref "U304") (pin "15") (pinfunction "PGND_15") (pintype "power_in"))
      (node (ref "U304") (pin "16") (pinfunction "PGND_16") (pintype "power_in"))
      (node (ref "U304") (pin "17") (pinfunction "EP_17") (pintype "power_in"))
      (node (ref "U304") (pin "5") (pinfunction "FB_5") (pintype "input"))
      (node (ref "U304") (pin "6") (pinfunction "AGND_6") (pintype "power_in"))
      (node (ref "U304") (pin "7") (pinfunction "FSW_7") (pintype "input"))
      (node (ref "U304") (pin "8") (pinfunction "DEF_8") (pintype "input"))
    )
    (net (code "35") (name "VDD") (class "Default")
      (node (ref "C310") (pin "1") (pinfunction "1_1") (pintype "passive"))
      (node (ref "D303") (pin "1") (pinfunction "K_1") (pintype "passive"))
      (node (ref "U301") (pin "1") (pinfunction "VDD_1") (pintype "power_in"))
      (node (ref "U302") (pin "4") (pinfunction "C_4") (pintype "passive"))
    )
    (net (code "36") (name "unconnected-(U305-NC-Pad4)") (class "Default")
      (node (ref "U305") (pin "4") (pinfunction "NC_4") (pintype "passive"))
    )
    (net (code "37") (name "unconnected-(U305-NC-Pad5)") (class "Default")
      (node (ref "U305") (pin "5") (pinfunction "NC_5") (pintype "passive"))
    )
  )
)
